# 05_IMU.net
KiCad netlist of a schematic drawn in Altium Designer
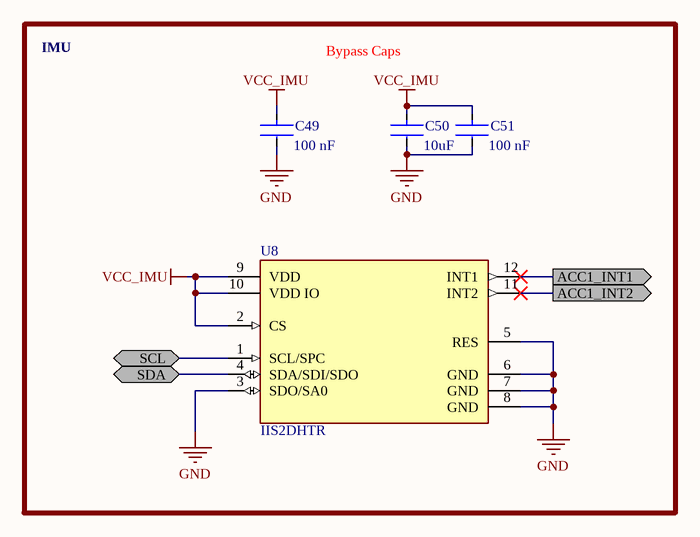
[diagram p0: 05_IMU.SchDoc]

(export (version "E")
  (design (tool "Eeschema 10.0.6"))
  (components
    (comp (ref "C49")
      (value "100 nF")
      (footprint "FP-CC0402-MFG")
      (description "CAP CER 0.1UF 16V X7R 0402")
      (fields (field (name "MANUFACTURER") "YAGEO") (field (name "TOLERANCE") "0.1"))
      (libsource (lib "Altium Content Vault") (part "11868f565c42a9108669ba33697ecf6"))
    )
    (comp (ref "C50")
      (value "10uF")
      (footprint "FP-C1608-080-MFG")
      (description "CAP CER 10UF 10V X5R 0603")
      (fields
        (field (name "MANUFACTURER PART NUMBER") "C1608X5R1A106K080AC")
        (field (name "OCTOPART") "https://octopart.com/c1608x5r1a106k080ac-tdk-26013468")
      )
      (libsource (lib "Altium Content Vault") (part "11868f565c42a9108669ba33697ecf6"))
    )
    (comp (ref "C51")
      (value "100 nF")
      (footprint "FP-CC0402-MFG")
      (description "CAP CER 0.1UF 16V X7R 0402")
      (fields (field (name "MANUFACTURER") "YAGEO") (field (name "TOLERANCE") "0.1"))
      (libsource (lib "Altium Content Vault") (part "11868f565c42a9108669ba33697ecf6"))
    )
    (comp (ref "U8")
      (value "IIS2DHTR")
      (footprint "FP-LGA-12-8365767-MFG")
      (description "ACCEL 2-16G I2C/SPI 12LGA")
      (fields
        (field (name "MANUFACTURER") "STMicroelectronics")
        (field (name "OCTOPART") "https://octopart.com/iis2dhtr-stmicroelectronics-58218805")
      )
      (libsource (lib "Altium Content Vault") (part "0aa3afda2c658fffe6312583959f072"))
    )
  )
  (nets
    (net (code "1") (name "/ACC1_INT1") (class "Default")
      (node (ref "U8") (pin "12") (pinfunction "INT1_12") (pintype "output+no_connect"))
    )
    (net (code "2") (name "/ACC1_INT2") (class "Default")
      (node (ref "U8") (pin "11") (pinfunction "INT2_11") (pintype "output+no_connect"))
    )
    (net (code "3") (name "/SCL") (class "Default")
      (node (ref "U8") (pin "1") (pinfunction "SCL/SPC_1") (pintype "input"))
    )
    (net (code "4") (name "/SDA") (class "Default")
      (node (ref "U8") (pin "4") (pinfunction "SDA/SDI/SDO_4") (pintype "bidirectional"))
    )
    (net (code "5") (name "GND") (class "Default")
      (node (ref "C49") (pin "2") (pinfunction "2_2") (pintype "passive"))
      (node (ref "C50") (pin "2") (pinfunction "2_2") (pintype "passive"))
      (node (ref "C51") (pin "2") (pinfunction "2_2") (pintype "passive"))
      (node (ref "U8") (pin "3") (pinfunction "SDO/SA0_3") (pintype "bidirectional"))
      (node (ref "U8") (pin "5") (pinfunction "RES_5") (pintype "passive"))
      (node (ref "U8") (pin "6") (pinfunction "GND_6") (pintype "power_in"))
      (node (ref "U8") (pin "7") (pinfunction "GND_7") (pintype "power_in"))
      (node (ref "U8") (pin "8") (pinfunction "GND_8") (pintype "power_in"))
    )
    (net (code "6") (name "VCC_IMU") (class "Default")
      (node (ref "C49") (pin "1") (pinfunction "1_1") (pintype "passive"))
      (node (ref "C50") (pin "1") (pinfunction "1_1") (pintype "passive"))
      (node (ref "C51") (pin "1") (pinfunction "1_1") (pintype "passive"))
      (node (ref "U8") (pin "10") (pinfunction "VDD_IO_10") (pintype "power_in"))
      (node (ref "U8") (pin "2") (pinfunction "CS_2") (pintype "input"))
      (node (ref "U8") (pin "9") (pinfunction "VDD_9") (pintype "power_in"))
    )
  )
)
